# Arduino-Pro-Mini_195x195inch_bike.net
KiCad netlist of a schematic drawn in EAGLE
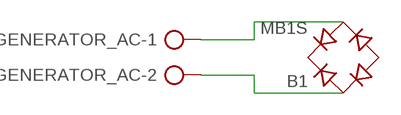
[diagram p0: schematic, sheet 1, part 1 of 2]
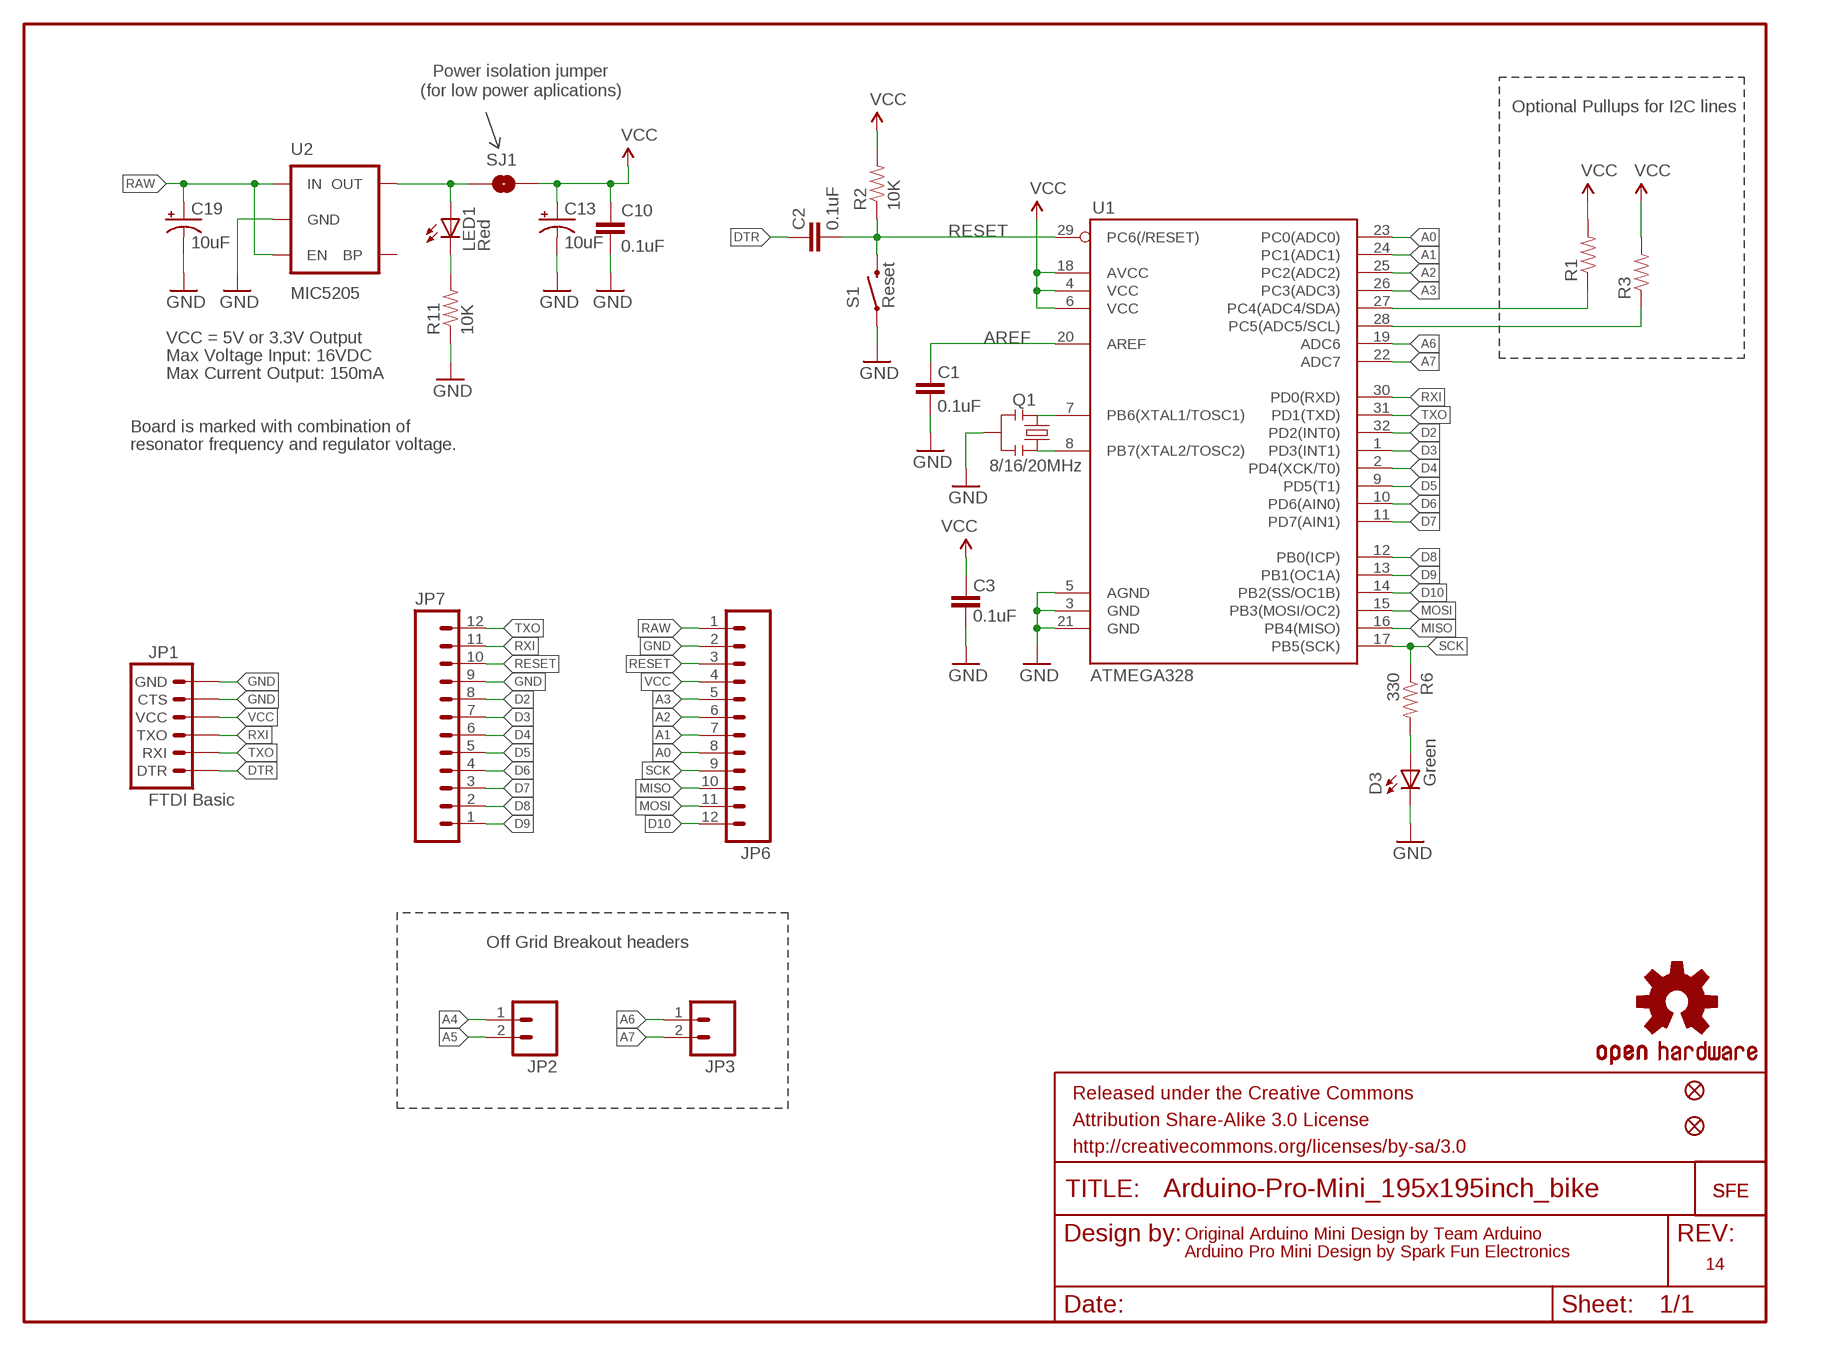
[diagram p1: schematic, sheet 1, part 2 of 2]

(export (version "E")
  (design (tool "Eeschema 10.0.6"))
  (components
    (comp (ref "B1")
      (value "MB1S")
      (footprint "eagle-import:SOIC-4")
      (libsource (lib "eagle-import") (part "MBS1"))
    )
    (comp (ref "C1")
      (value "0.1uF")
      (footprint "eagle-import:0603-CAP")
      (libsource (lib "eagle-import") (part "CAP0603-CAP"))
    )
    (comp (ref "C2")
      (value "0.1uF")
      (footprint "eagle-import:0603-CAP")
      (libsource (lib "eagle-import") (part "CAP0603-CAP"))
    )
    (comp (ref "C3")
      (value "0.1uF")
      (footprint "eagle-import:0603-CAP")
      (libsource (lib "eagle-import") (part "CAP0603-CAP"))
    )
    (comp (ref "C10")
      (value "0.1uF")
      (footprint "eagle-import:0603-CAP")
      (libsource (lib "eagle-import") (part "CAP0603-CAP"))
    )
    (comp (ref "C13")
      (value "10uF")
      (footprint "eagle-import:EIA3216")
      (libsource (lib "eagle-import") (part "CAP_POL1206"))
    )
    (comp (ref "C19")
      (value "10uF")
      (footprint "eagle-import:EIA3216")
      (libsource (lib "eagle-import") (part "CAP_POL1206"))
    )
    (comp (ref "D3")
      (value "Green")
      (footprint "eagle-import:0603-LED-ALT1")
      (libsource (lib "eagle-import") (part "LED"))
    )
    (comp (ref "FRAME1")
      (value "FRAME-LETTER")
      (footprint "eagle-import:CREATIVE_COMMONS")
      (libsource (lib "eagle-import") (part "FRAME-LETTER"))
    )
    (comp (ref "GENERATOR_AC")
      (value "AK300/2")
      (footprint "eagle-import:AK300_2")
      (libsource (lib "eagle-import") (part "AK300/2"))
    )
    (comp (ref "JP1")
      (value "FTDI Basic")
      (footprint "eagle-import:1X06")
      (libsource (lib "eagle-import") (part "ARDUINO_SERIAL_PROGRAMPTH"))
    )
    (comp (ref "JP2")
      (value "M02PTH")
      (footprint "eagle-import:1X02")
      (libsource (lib "eagle-import") (part "M02PTH"))
    )
    (comp (ref "JP3")
      (value "M02PTH")
      (footprint "eagle-import:1X02")
      (libsource (lib "eagle-import") (part "M02PTH"))
    )
    (comp (ref "JP5")
      (value "FIDUCIALUFIDUCIAL")
      (footprint "eagle-import:MICRO-FIDUCIAL")
      (libsource (lib "eagle-import") (part "FIDUCIALUFIDUCIAL"))
    )
    (comp (ref "JP6")
      (value "M12PTH")
      (footprint "eagle-import:1X12")
      (libsource (lib "eagle-import") (part "M12PTH"))
    )
    (comp (ref "JP7")
      (value "M12PTH")
      (footprint "eagle-import:1X12")
      (libsource (lib "eagle-import") (part "M12PTH"))
    )
    (comp (ref "JP8")
      (value "FIDUCIALUFIDUCIAL")
      (footprint "eagle-import:MICRO-FIDUCIAL")
      (libsource (lib "eagle-import") (part "FIDUCIALUFIDUCIAL"))
    )
    (comp (ref "LED1")
      (value "Red")
      (footprint "eagle-import:0603-LED-ALT1")
      (libsource (lib "eagle-import") (part "LED"))
    )
    (comp (ref "Q1")
      (value "8/16/20MHz")
      (footprint "eagle-import:RESONATOR-SMD-1_1")
      (libsource (lib "eagle-import") (part "RESONATOR1{colon}1"))
    )
    (comp (ref "R1")
      (value "RESISTOR0603-RES")
      (footprint "eagle-import:0603-RES")
      (libsource (lib "eagle-import") (part "RESISTOR0603-RES"))
    )
    (comp (ref "R2")
      (value "10K")
      (footprint "eagle-import:0603-RES")
      (libsource (lib "eagle-import") (part "RESISTOR0603-RES"))
    )
    (comp (ref "R3")
      (value "RESISTOR0603-RES")
      (footprint "eagle-import:0603-RES")
      (libsource (lib "eagle-import") (part "RESISTOR0603-RES"))
    )
    (comp (ref "R6")
      (value "330")
      (footprint "eagle-import:0603-RES")
      (libsource (lib "eagle-import") (part "RESISTOR0603-RES"))
    )
    (comp (ref "R11")
      (value "10K")
      (footprint "eagle-import:0603-RES")
      (libsource (lib "eagle-import") (part "RESISTOR0603-RES"))
    )
    (comp (ref "S1")
      (value "Reset")
      (footprint "eagle-import:TACTILE-SWITCH-SMD-ALT01")
      (libsource (lib "eagle-import") (part "SWITCH-MOMENTARY-2SMD-ALT01"))
    )
    (comp (ref "SJ1")
      (value "SOLDERJUMPERNC")
      (footprint "eagle-import:SJ_2S")
      (libsource (lib "eagle-import") (part "SOLDERJUMPERNC"))
    )
    (comp (ref "U$1")
      (value "LOGO-SFESK")
      (footprint "eagle-import:SFE-LOGO-FLAME")
      (libsource (lib "eagle-import") (part "LOGO-SFESK"))
    )
    (comp (ref "U$3")
      (value "OSHW-LOGOS")
      (footprint "eagle-import:OSHW-LOGO-S")
      (libsource (lib "eagle-import") (part "OSHW-LOGOS"))
    )
    (comp (ref "U$11")
      (value "LOGO-SFENEW")
      (footprint "eagle-import:SFE-NEW-WEBLOGO")
      (libsource (lib "eagle-import") (part "LOGO-SFENEW"))
    )
    (comp (ref "U1")
      (value "ATMEGA328")
      (footprint "eagle-import:TQFP32-08")
      (libsource (lib "eagle-import") (part "ATMEGA168"))
    )
    (comp (ref "U2")
      (value "MIC5205")
      (footprint "eagle-import:SOT23-5")
      (libsource (lib "eagle-import") (part "V_REG_LDOSMD"))
    )
  )
  (nets
    (net (code "1") (name "/AREF") (class "Default")
      (node (ref "C1") (pin "2") (pinfunction "2_2") (pintype "passive"))
      (node (ref "U1") (pin "20") (pinfunction "AREF_20") (pintype "bidirectional"))
    )
    (net (code "2") (name "A0") (class "Default")
      (node (ref "JP6") (pin "8") (pinfunction "8_8") (pintype "passive"))
      (node (ref "U1") (pin "23") (pinfunction "PC0(ADC0)_23") (pintype "bidirectional"))
    )
    (net (code "3") (name "A1") (class "Default")
      (node (ref "JP6") (pin "7") (pinfunction "7_7") (pintype "passive"))
      (node (ref "U1") (pin "24") (pinfunction "PC1(ADC1)_24") (pintype "bidirectional"))
    )
    (net (code "4") (name "A2") (class "Default")
      (node (ref "JP6") (pin "6") (pinfunction "6_6") (pintype "passive"))
      (node (ref "U1") (pin "25") (pinfunction "PC2(ADC2)_25") (pintype "bidirectional"))
    )
    (net (code "5") (name "A3") (class "Default")
      (node (ref "JP6") (pin "5") (pinfunction "5_5") (pintype "passive"))
      (node (ref "U1") (pin "26") (pinfunction "PC3(ADC3)_26") (pintype "bidirectional"))
    )
    (net (code "6") (name "A4") (class "Default")
      (node (ref "JP2") (pin "1") (pinfunction "1_1") (pintype "passive"))
      (node (ref "R1") (pin "1") (pinfunction "1_1") (pintype "passive"))
      (node (ref "U1") (pin "27") (pinfunction "PC4(ADC4/SDA)_27") (pintype "bidirectional"))
    )
    (net (code "7") (name "A5") (class "Default")
      (node (ref "JP2") (pin "2") (pinfunction "2_2") (pintype "passive"))
      (node (ref "R3") (pin "1") (pinfunction "1_1") (pintype "passive"))
      (node (ref "U1") (pin "28") (pinfunction "PC5(ADC5/SCL)_28") (pintype "bidirectional"))
    )
    (net (code "8") (name "A6") (class "Default")
      (node (ref "JP3") (pin "1") (pinfunction "1_1") (pintype "passive"))
      (node (ref "U1") (pin "19") (pinfunction "ADC6_19") (pintype "bidirectional"))
    )
    (net (code "9") (name "A7") (class "Default")
      (node (ref "JP3") (pin "2") (pinfunction "2_2") (pintype "passive"))
      (node (ref "U1") (pin "22") (pinfunction "ADC7_22") (pintype "bidirectional"))
    )
    (net (code "10") (name "D2") (class "Default")
      (node (ref "JP7") (pin "8") (pinfunction "8_8") (pintype "passive"))
      (node (ref "U1") (pin "32") (pinfunction "PD2(INT0)_32") (pintype "bidirectional"))
    )
    (net (code "11") (name "D3") (class "Default")
      (node (ref "JP7") (pin "7") (pinfunction "7_7") (pintype "passive"))
      (node (ref "U1") (pin "1") (pinfunction "PD3(INT1)_1") (pintype "bidirectional"))
    )
    (net (code "12") (name "D4") (class "Default")
      (node (ref "JP7") (pin "6") (pinfunction "6_6") (pintype "passive"))
      (node (ref "U1") (pin "2") (pinfunction "PD4(XCK/T0)_2") (pintype "bidirectional"))
    )
    (net (code "13") (name "D5") (class "Default")
      (node (ref "JP7") (pin "5") (pinfunction "5_5") (pintype "passive"))
      (node (ref "U1") (pin "9") (pinfunction "PD5(T1)_9") (pintype "bidirectional"))
    )
    (net (code "14") (name "D6") (class "Default")
      (node (ref "JP7") (pin "4") (pinfunction "4_4") (pintype "passive"))
      (node (ref "U1") (pin "10") (pinfunction "PD6(AIN0)_10") (pintype "bidirectional"))
    )
    (net (code "15") (name "D7") (class "Default")
      (node (ref "JP7") (pin "3") (pinfunction "3_3") (pintype "passive"))
      (node (ref "U1") (pin "11") (pinfunction "PD7(AIN1)_11") (pintype "bidirectional"))
    )
    (net (code "16") (name "D8") (class "Default")
      (node (ref "JP7") (pin "2") (pinfunction "2_2") (pintype "passive"))
      (node (ref "U1") (pin "12") (pinfunction "PB0(ICP)_12") (pintype "bidirectional"))
    )
    (net (code "17") (name "D9") (class "Default")
      (node (ref "JP7") (pin "1") (pinfunction "1_1") (pintype "passive"))
      (node (ref "U1") (pin "13") (pinfunction "PB1(OC1A)_13") (pintype "bidirectional"))
    )
    (net (code "18") (name "D10") (class "Default")
      (node (ref "JP6") (pin "12") (pinfunction "12_12") (pintype "passive"))
      (node (ref "U1") (pin "14") (pinfunction "PB2(SS/OC1B)_14") (pintype "bidirectional"))
    )
    (net (code "19") (name "DTR") (class "Default")
      (node (ref "C2") (pin "2") (pinfunction "2_2") (pintype "passive"))
      (node (ref "JP1") (pin "1") (pinfunction "DTR_1") (pintype "passive"))
    )
    (net (code "20") (name "GND") (class "Default")
      (node (ref "C1") (pin "1") (pinfunction "1_1") (pintype "passive"))
      (node (ref "C10") (pin "2") (pinfunction "2_2") (pintype "passive"))
      (node (ref "C13") (pin "C") (pinfunction "-_C") (pintype "passive"))
      (node (ref "C19") (pin "C") (pinfunction "-_C") (pintype "passive"))
      (node (ref "C3") (pin "1") (pinfunction "1_1") (pintype "passive"))
      (node (ref "D3") (pin "C") (pinfunction "C_C") (pintype "passive"))
      (node (ref "JP1") (pin "5") (pinfunction "CTS_5") (pintype "passive"))
      (node (ref "JP1") (pin "6") (pinfunction "GND_6") (pintype "passive"))
      (node (ref "JP6") (pin "2") (pinfunction "2_2") (pintype "passive"))
      (node (ref "JP7") (pin "9") (pinfunction "9_9") (pintype "passive"))
      (node (ref "Q1") (pin "2") (pinfunction "2_2") (pintype "passive"))
      (node (ref "R11") (pin "1") (pinfunction "1_1") (pintype "passive"))
      (node (ref "S1") (pin "1") (pinfunction "1_1") (pintype "passive"))
      (node (ref "S1") (pin "2") (pinfunction "1_2") (pintype "passive"))
      (node (ref "U1") (pin "21") (pinfunction "GND_21") (pintype "bidirectional"))
      (node (ref "U1") (pin "3") (pinfunction "GND_3") (pintype "bidirectional"))
      (node (ref "U1") (pin "5") (pinfunction "AGND_5") (pintype "bidirectional"))
      (node (ref "U2") (pin "2") (pinfunction "GND_2") (pintype "input"))
    )
    (net (code "21") (name "MISO") (class "Default")
      (node (ref "JP6") (pin "10") (pinfunction "10_10") (pintype "passive"))
      (node (ref "U1") (pin "16") (pinfunction "PB4(MISO)_16") (pintype "bidirectional"))
    )
    (net (code "22") (name "MOSI") (class "Default")
      (node (ref "JP6") (pin "11") (pinfunction "11_11") (pintype "passive"))
      (node (ref "U1") (pin "15") (pinfunction "PB3(MOSI/OC2)_15") (pintype "bidirectional"))
    )
    (net (code "23") (name "Net-(B1-AC1)") (class "Default")
      (node (ref "B1") (pin "~1") (pinfunction "AC1_~1") (pintype "passive"))
      (node (ref "GENERATOR_AC") (pin "2") (pinfunction "KL_2") (pintype "passive"))
    )
    (net (code "24") (name "Net-(B1-AC2)") (class "Default")
      (node (ref "B1") (pin "~2") (pinfunction "AC2_~2") (pintype "passive"))
      (node (ref "GENERATOR_AC") (pin "1") (pinfunction "KL_1") (pintype "passive"))
    )
    (net (code "25") (name "Net-(D3-PadA)") (class "Default")
      (node (ref "D3") (pin "A") (pinfunction "A_A") (pintype "passive"))
      (node (ref "R6") (pin "2") (pinfunction "2_2") (pintype "passive"))
    )
    (net (code "26") (name "Net-(LED1-PadC)") (class "Default")
      (node (ref "LED1") (pin "C") (pinfunction "C_C") (pintype "passive"))
      (node (ref "R11") (pin "2") (pinfunction "2_2") (pintype "passive"))
    )
    (net (code "27") (name "Net-(U1-PB6(XTAL1{slash}TOSC1))") (class "Default")
      (node (ref "Q1") (pin "1") (pinfunction "1_1") (pintype "passive"))
      (node (ref "U1") (pin "7") (pinfunction "PB6(XTAL1/TOSC1)_7") (pintype "bidirectional"))
    )
    (net (code "28") (name "Net-(U1-PB7(XTAL2{slash}TOSC2))") (class "Default")
      (node (ref "Q1") (pin "3") (pinfunction "3_3") (pintype "passive"))
      (node (ref "U1") (pin "8") (pinfunction "PB7(XTAL2/TOSC2)_8") (pintype "bidirectional"))
    )
    (net (code "29") (name "Net-(U2-OUT)") (class "Default")
      (node (ref "LED1") (pin "A") (pinfunction "A_A") (pintype "passive"))
      (node (ref "SJ1") (pin "1") (pinfunction "1_1") (pintype "passive"))
      (node (ref "U2") (pin "5") (pinfunction "OUT_5") (pintype "passive"))
    )
    (net (code "30") (name "RAW") (class "Default")
      (node (ref "C19") (pin "A") (pinfunction "+_A") (pintype "passive"))
      (node (ref "JP6") (pin "1") (pinfunction "1_1") (pintype "passive"))
      (node (ref "U2") (pin "1") (pinfunction "IN_1") (pintype "input"))
      (node (ref "U2") (pin "3") (pinfunction "EN_3") (pintype "input"))
    )
    (net (code "31") (name "RESET") (class "Default")
      (node (ref "C2") (pin "1") (pinfunction "1_1") (pintype "passive"))
      (node (ref "JP6") (pin "3") (pinfunction "3_3") (pintype "passive"))
      (node (ref "JP7") (pin "10") (pinfunction "10_10") (pintype "passive"))
      (node (ref "R2") (pin "1") (pinfunction "1_1") (pintype "passive"))
      (node (ref "S1") (pin "3") (pinfunction "2_3") (pintype "passive"))
      (node (ref "S1") (pin "4") (pinfunction "2_4") (pintype "passive"))
      (node (ref "U1") (pin "29") (pinfunction "PC6(/RESET)_29") (pintype "bidirectional"))
    )
    (net (code "32") (name "RXI") (class "Default")
      (node (ref "JP1") (pin "3") (pinfunction "TXO_3") (pintype "passive"))
      (node (ref "JP7") (pin "11") (pinfunction "11_11") (pintype "passive"))
      (node (ref "U1") (pin "30") (pinfunction "PD0(RXD)_30") (pintype "bidirectional"))
    )
    (net (code "33") (name "SCK") (class "Default")
      (node (ref "JP6") (pin "9") (pinfunction "9_9") (pintype "passive"))
      (node (ref "R6") (pin "1") (pinfunction "1_1") (pintype "passive"))
      (node (ref "U1") (pin "17") (pinfunction "PB5(SCK)_17") (pintype "bidirectional"))
    )
    (net (code "34") (name "TXO") (class "Default")
      (node (ref "JP1") (pin "2") (pinfunction "RXI_2") (pintype "passive"))
      (node (ref "JP7") (pin "12") (pinfunction "12_12") (pintype "passive"))
      (node (ref "U1") (pin "31") (pinfunction "PD1(TXD)_31") (pintype "bidirectional"))
    )
    (net (code "35") (name "VCC") (class "Default")
      (node (ref "C10") (pin "1") (pinfunction "1_1") (pintype "passive"))
      (node (ref "C13") (pin "A") (pinfunction "+_A") (pintype "passive"))
      (node (ref "C3") (pin "2") (pinfunction "2_2") (pintype "passive"))
      (node (ref "JP1") (pin "4") (pinfunction "VCC_4") (pintype "passive"))
      (node (ref "JP6") (pin "4") (pinfunction "4_4") (pintype "passive"))
      (node (ref "R1") (pin "2") (pinfunction "2_2") (pintype "passive"))
      (node (ref "R2") (pin "2") (pinfunction "2_2") (pintype "passive"))
      (node (ref "R3") (pin "2") (pinfunction "2_2") (pintype "passive"))
      (node (ref "SJ1") (pin "2") (pinfunction "2_2") (pintype "passive"))
      (node (ref "U1") (pin "18") (pinfunction "AVCC_18") (pintype "bidirectional"))
      (node (ref "U1") (pin "4") (pinfunction "VCC_4") (pintype "bidirectional"))
      (node (ref "U1") (pin "6") (pinfunction "VCC_6") (pintype "bidirectional"))
    )
    (net (code "36") (name "unconnected-(B1-Pad+)") (class "Default")
      (node (ref "B1") (pin "+") (pinfunction "+_+") (pintype "passive"))
    )
    (net (code "37") (name "unconnected-(B1-Pad-)") (class "Default")
      (node (ref "B1") (pin "-") (pinfunction "-_-") (pintype "passive"))
    )
    (net (code "38") (name "unconnected-(U2-BP-Pad4)") (class "Default")
      (node (ref "U2") (pin "4") (pinfunction "BP_4") (pintype "input"))
    )
  )
)
